# design.net
KiCad netlist of a schematic drawn in Altium Designer
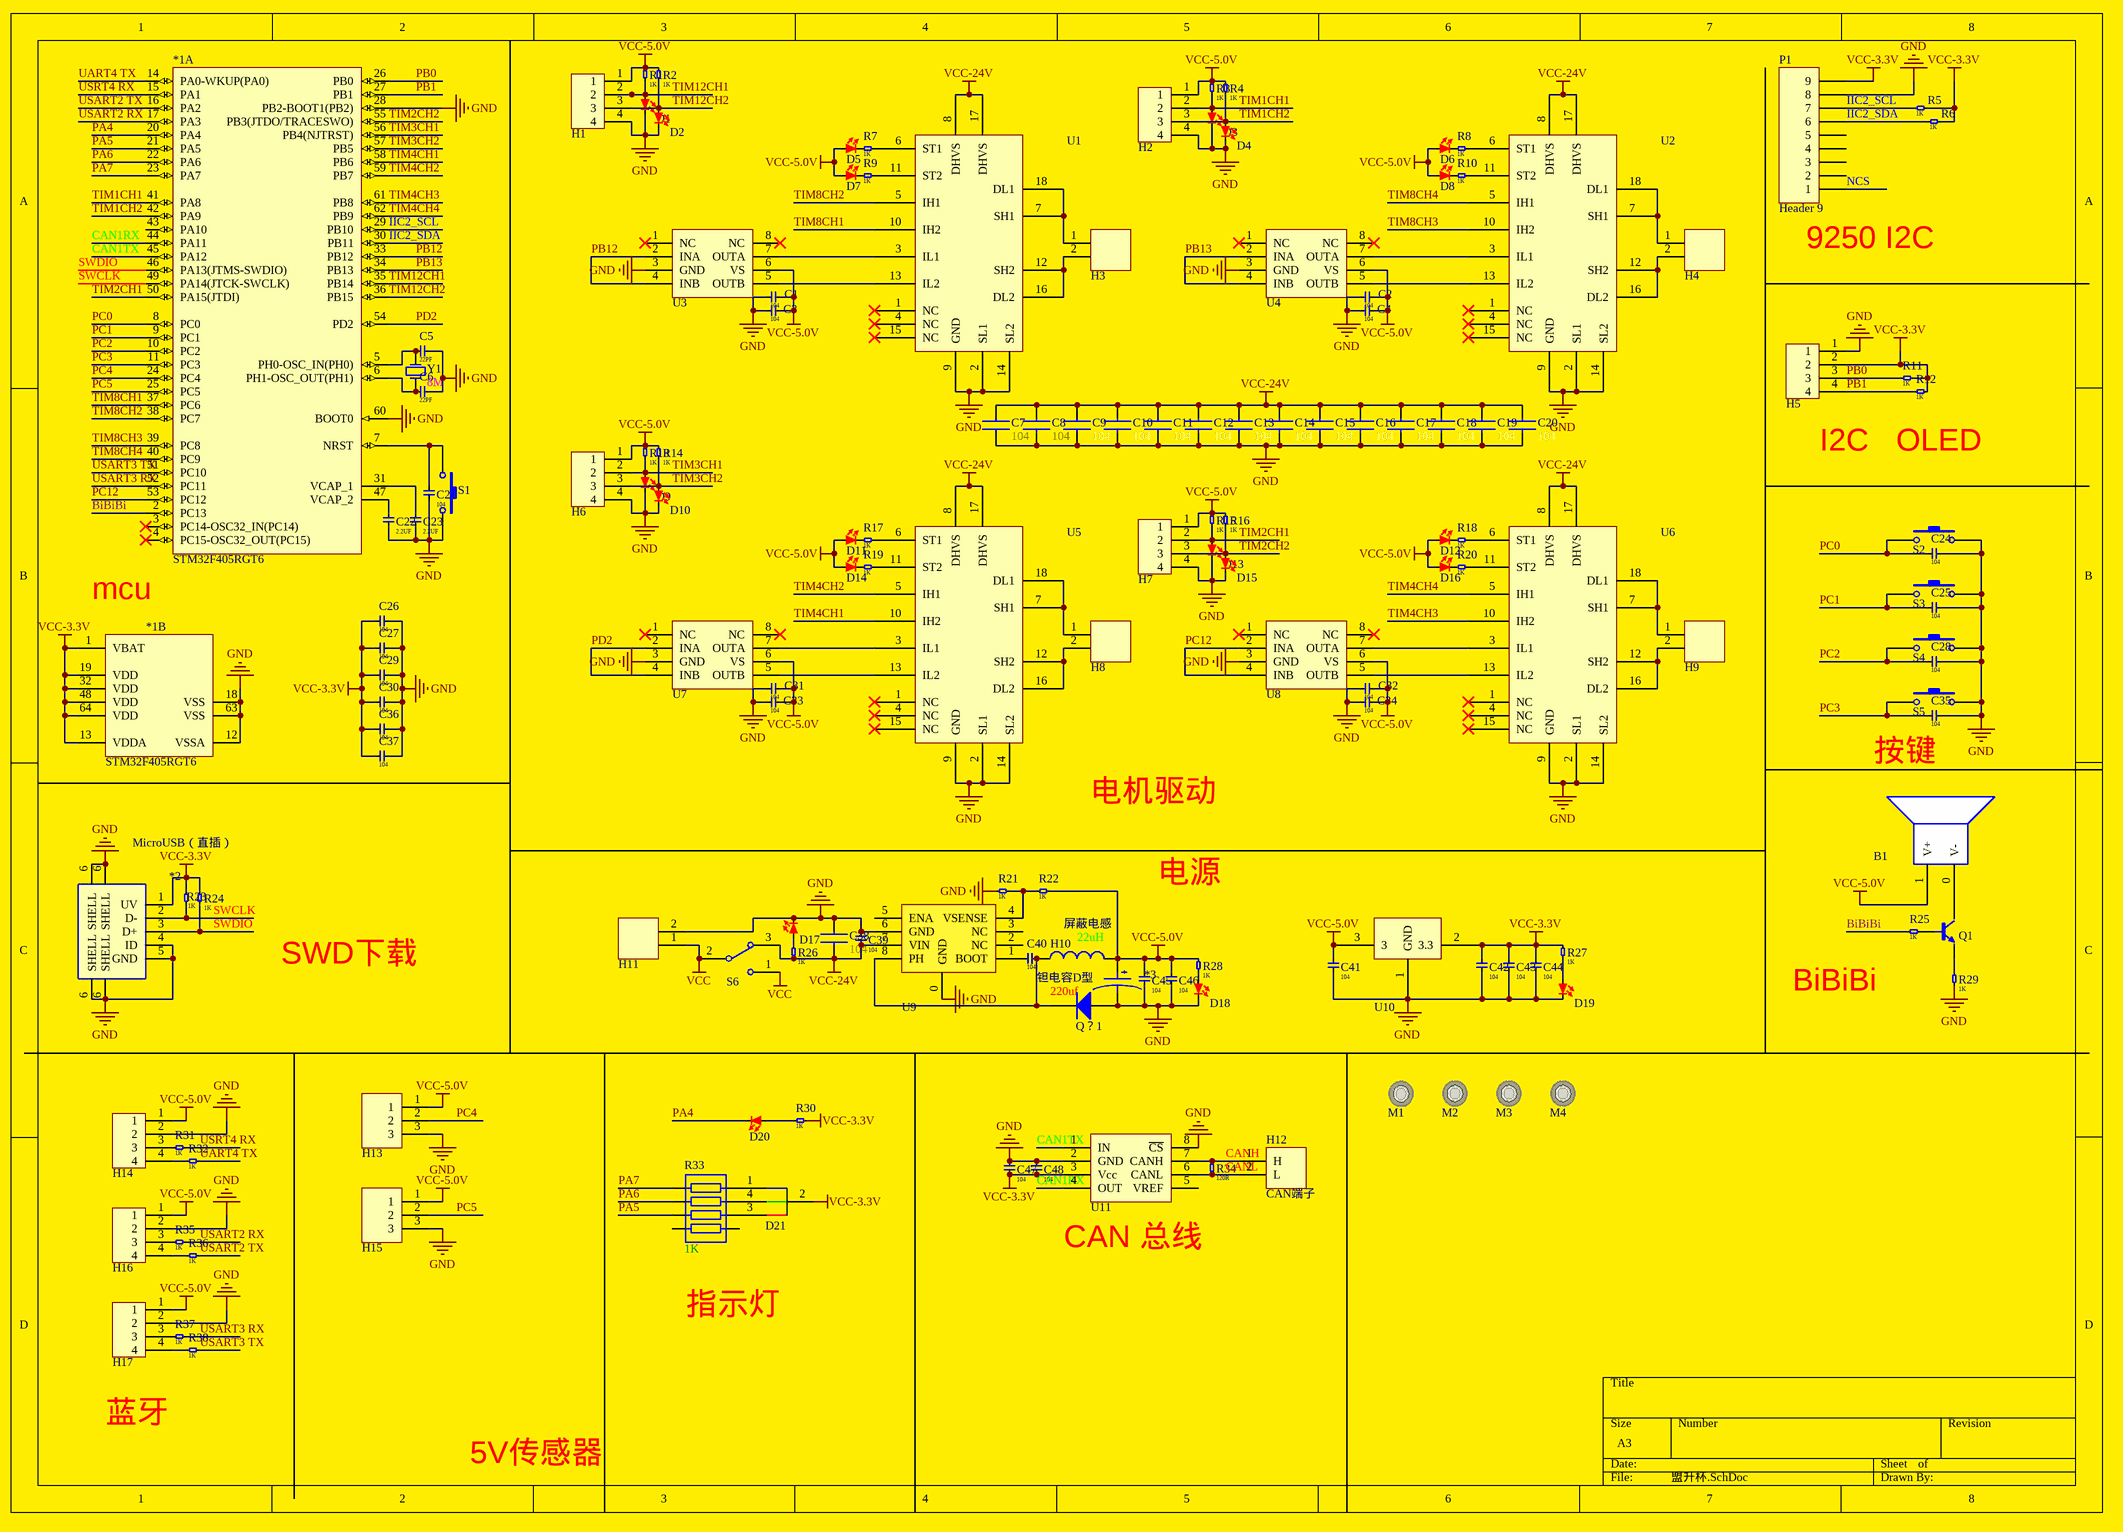
[diagram p0: 盟升杯.SchDoc]

(export (version "E")
  (design (tool "Eeschema 10.0.6"))
  (components
    (comp (ref "*1")
      (value "STM32F405RGT6")
      (footprint "LQFP_64P")
      (libsource (lib "固执啊啊啊啊啊（方林的封装库）7.24") (part "STM32F405RGT6"))
    )
    (comp (ref "*2")
      (value "MicroUSB（直插）")
      (footprint "MicroUSB（直插）")
      (libsource (lib "固执啊啊啊啊啊（方林的封装库）7.24") (part "MicroUSB（直插）"))
    )
    (comp (ref "*3")
      (value "钽电容D型")
      (footprint "钽电容D型")
      (fields (field (name "ALTIUM_UNNAMED_1") "220uf"))
      (libsource (lib "固执啊啊啊啊啊（方林的封装库）7.24") (part "钽电容D型"))
    )
    (comp (ref "B1")
      (value "KLJ-9032")
      (footprint "KLJ-9032")
      (description "贴片蜂鸣器")
      (libsource (lib "固执啊啊啊啊啊（方林的封装库）7.24") (part "KLJ-9032"))
    )
    (comp (ref "C1")
      (value "CAP0603")
      (footprint "CAP0603")
      (fields (field (name "ALTIUM_UNNAMED_1") "104"))
      (libsource (lib "固执啊啊啊啊啊（方林的封装库）7.24") (part "CAP0603"))
    )
    (comp (ref "C2")
      (value "CAP0603")
      (footprint "CAP0603")
      (fields (field (name "ALTIUM_UNNAMED_1") "104"))
      (libsource (lib "固执啊啊啊啊啊（方林的封装库）7.24") (part "CAP0603"))
    )
    (comp (ref "C3")
      (value "CAP0603")
      (footprint "CAP0603")
      (fields (field (name "ALTIUM_UNNAMED_1") "104"))
      (libsource (lib "固执啊啊啊啊啊（方林的封装库）7.24") (part "CAP0603"))
    )
    (comp (ref "C4")
      (value "CAP0603")
      (footprint "CAP0603")
      (fields (field (name "ALTIUM_UNNAMED_1") "104"))
      (libsource (lib "固执啊啊啊啊啊（方林的封装库）7.24") (part "CAP0603"))
    )
    (comp (ref "C5")
      (value "CAP0603")
      (footprint "CAP0603")
      (fields (field (name "ALTIUM_UNNAMED_1") "22PF"))
      (libsource (lib "固执啊啊啊啊啊（方林的封装库）7.24") (part "CAP0603"))
    )
    (comp (ref "C6")
      (value "CAP0603")
      (footprint "CAP0603")
      (fields (field (name "ALTIUM_UNNAMED_1") "22PF"))
      (libsource (lib "固执啊啊啊啊啊（方林的封装库）7.24") (part "CAP0603"))
    )
    (comp (ref "C7")
      (value "CAP1812")
      (footprint "CAP1812")
      (fields (field (name "ALTIUM_UNNAMED_1") "104"))
      (libsource (lib "固执啊啊啊啊啊（方林的封装库）7.24") (part "CAP1812"))
    )
    (comp (ref "C8")
      (value "CAP1812")
      (footprint "CAP1812")
      (fields (field (name "ALTIUM_UNNAMED_1") "104"))
      (libsource (lib "固执啊啊啊啊啊（方林的封装库）7.24") (part "CAP1812"))
    )
    (comp (ref "C9")
      (value "CAP1210")
      (footprint "CAP1210")
      (fields (field (name "ALTIUM_UNNAMED_1") "104"))
      (libsource (lib "固执啊啊啊啊啊（方林的封装库）7.24") (part "CAP1210"))
    )
    (comp (ref "C10")
      (value "CAP1210")
      (footprint "CAP1210")
      (fields (field (name "ALTIUM_UNNAMED_1") "104"))
      (libsource (lib "固执啊啊啊啊啊（方林的封装库）7.24") (part "CAP1210"))
    )
    (comp (ref "C11")
      (value "CAP1210")
      (footprint "CAP1210")
      (fields (field (name "ALTIUM_UNNAMED_1") "104"))
      (libsource (lib "固执啊啊啊啊啊（方林的封装库）7.24") (part "CAP1210"))
    )
    (comp (ref "C12")
      (value "CAP1210")
      (footprint "CAP1210")
      (fields (field (name "ALTIUM_UNNAMED_1") "104"))
      (libsource (lib "固执啊啊啊啊啊（方林的封装库）7.24") (part "CAP1210"))
    )
    (comp (ref "C13")
      (value "CAP1210")
      (footprint "CAP1210")
      (fields (field (name "ALTIUM_UNNAMED_1") "104"))
      (libsource (lib "固执啊啊啊啊啊（方林的封装库）7.24") (part "CAP1210"))
    )
    (comp (ref "C14")
      (value "CAP1210")
      (footprint "CAP1210")
      (fields (field (name "ALTIUM_UNNAMED_1") "104"))
      (libsource (lib "固执啊啊啊啊啊（方林的封装库）7.24") (part "CAP1210"))
    )
    (comp (ref "C15")
      (value "CAP1210")
      (footprint "CAP1210")
      (fields (field (name "ALTIUM_UNNAMED_1") "104"))
      (libsource (lib "固执啊啊啊啊啊（方林的封装库）7.24") (part "CAP1210"))
    )
    (comp (ref "C16")
      (value "CAP1210")
      (footprint "CAP1210")
      (fields (field (name "ALTIUM_UNNAMED_1") "104"))
      (libsource (lib "固执啊啊啊啊啊（方林的封装库）7.24") (part "CAP1210"))
    )
    (comp (ref "C17")
      (value "CAP1210")
      (footprint "CAP1210")
      (fields (field (name "ALTIUM_UNNAMED_1") "104"))
      (libsource (lib "固执啊啊啊啊啊（方林的封装库）7.24") (part "CAP1210"))
    )
    (comp (ref "C18")
      (value "CAP1210")
      (footprint "CAP1210")
      (fields (field (name "ALTIUM_UNNAMED_1") "104"))
      (libsource (lib "固执啊啊啊啊啊（方林的封装库）7.24") (part "CAP1210"))
    )
    (comp (ref "C19")
      (value "CAP1210")
      (footprint "CAP1210")
      (fields (field (name "ALTIUM_UNNAMED_1") "104"))
      (libsource (lib "固执啊啊啊啊啊（方林的封装库）7.24") (part "CAP1210"))
    )
    (comp (ref "C20")
      (value "CAP1210")
      (footprint "CAP1210")
      (fields (field (name "ALTIUM_UNNAMED_1") "104"))
      (libsource (lib "固执啊啊啊啊啊（方林的封装库）7.24") (part "CAP1210"))
    )
    (comp (ref "C21")
      (value "CAP0603")
      (footprint "CAP0603")
      (fields (field (name "ALTIUM_UNNAMED_1") "104"))
      (libsource (lib "固执啊啊啊啊啊（方林的封装库）7.24") (part "CAP0603"))
    )
    (comp (ref "C22")
      (value "CAP0603")
      (footprint "CAP0603")
      (fields (field (name "ALTIUM_UNNAMED_1") "2.2UF"))
      (libsource (lib "固执啊啊啊啊啊（方林的封装库）7.24") (part "CAP0603"))
    )
    (comp (ref "C23")
      (value "CAP0603")
      (footprint "CAP0603")
      (fields (field (name "ALTIUM_UNNAMED_1") "2.2UF"))
      (libsource (lib "固执啊啊啊啊啊（方林的封装库）7.24") (part "CAP0603"))
    )
    (comp (ref "C24")
      (value "CAP0603")
      (footprint "CAP0603")
      (fields (field (name "ALTIUM_UNNAMED_1") "104"))
      (libsource (lib "固执啊啊啊啊啊（方林的封装库）7.24") (part "CAP0603"))
    )
    (comp (ref "C25")
      (value "CAP0603")
      (footprint "CAP0603")
      (fields (field (name "ALTIUM_UNNAMED_1") "104"))
      (libsource (lib "固执啊啊啊啊啊（方林的封装库）7.24") (part "CAP0603"))
    )
    (comp (ref "C26")
      (value "CAP0603")
      (footprint "CAP0603")
      (fields (field (name "ALTIUM_UNNAMED_1") "104"))
      (libsource (lib "固执啊啊啊啊啊（方林的封装库）7.24") (part "CAP0603"))
    )
    (comp (ref "C27")
      (value "CAP0603")
      (footprint "CAP0603")
      (fields (field (name "ALTIUM_UNNAMED_1") "104"))
      (libsource (lib "固执啊啊啊啊啊（方林的封装库）7.24") (part "CAP0603"))
    )
    (comp (ref "C28")
      (value "CAP0603")
      (footprint "CAP0603")
      (fields (field (name "ALTIUM_UNNAMED_1") "104"))
      (libsource (lib "固执啊啊啊啊啊（方林的封装库）7.24") (part "CAP0603"))
    )
    (comp (ref "C29")
      (value "CAP0603")
      (footprint "CAP0603")
      (fields (field (name "ALTIUM_UNNAMED_1") "104"))
      (libsource (lib "固执啊啊啊啊啊（方林的封装库）7.24") (part "CAP0603"))
    )
    (comp (ref "C30")
      (value "CAP0603")
      (footprint "CAP0603")
      (fields (field (name "ALTIUM_UNNAMED_1") "104"))
      (libsource (lib "固执啊啊啊啊啊（方林的封装库）7.24") (part "CAP0603"))
    )
    (comp (ref "C31")
      (value "CAP0603")
      (footprint "CAP0603")
      (fields (field (name "ALTIUM_UNNAMED_1") "104"))
      (libsource (lib "固执啊啊啊啊啊（方林的封装库）7.24") (part "CAP0603"))
    )
    (comp (ref "C32")
      (value "CAP0603")
      (footprint "CAP0603")
      (fields (field (name "ALTIUM_UNNAMED_1") "104"))
      (libsource (lib "固执啊啊啊啊啊（方林的封装库）7.24") (part "CAP0603"))
    )
    (comp (ref "C33")
      (value "CAP0603")
      (footprint "CAP0603")
      (fields (field (name "ALTIUM_UNNAMED_1") "104"))
      (libsource (lib "固执啊啊啊啊啊（方林的封装库）7.24") (part "CAP0603"))
    )
    (comp (ref "C34")
      (value "CAP0603")
      (footprint "CAP0603")
      (fields (field (name "ALTIUM_UNNAMED_1") "104"))
      (libsource (lib "固执啊啊啊啊啊（方林的封装库）7.24") (part "CAP0603"))
    )
    (comp (ref "C35")
      (value "CAP0603")
      (footprint "CAP0603")
      (fields (field (name "ALTIUM_UNNAMED_1") "104"))
      (libsource (lib "固执啊啊啊啊啊（方林的封装库）7.24") (part "CAP0603"))
    )
    (comp (ref "C36")
      (value "CAP0603")
      (footprint "CAP0603")
      (fields (field (name "ALTIUM_UNNAMED_1") "104"))
      (libsource (lib "固执啊啊啊啊啊（方林的封装库）7.24") (part "CAP0603"))
    )
    (comp (ref "C37")
      (value "CAP0603")
      (footprint "CAP0603")
      (fields (field (name "ALTIUM_UNNAMED_1") "104"))
      (libsource (lib "固执啊啊啊啊啊（方林的封装库）7.24") (part "CAP0603"))
    )
    (comp (ref "C38")
      (value "CAP1812")
      (footprint "CAP1812")
      (fields (field (name "ALTIUM_UNNAMED_1") "104"))
      (libsource (lib "固执啊啊啊啊啊（方林的封装库）7.24") (part "CAP1812"))
    )
    (comp (ref "C39")
      (value "CAP0603")
      (footprint "CAP0603")
      (fields (field (name "ALTIUM_UNNAMED_1") "104"))
      (libsource (lib "固执啊啊啊啊啊（方林的封装库）7.24") (part "CAP0603"))
    )
    (comp (ref "C40")
      (value "CAP0603")
      (footprint "CAP0603")
      (fields (field (name "ALTIUM_UNNAMED_1") "104"))
      (libsource (lib "固执啊啊啊啊啊（方林的封装库）7.24") (part "CAP0603"))
    )
    (comp (ref "C41")
      (value "CAP0603")
      (footprint "CAP0603")
      (fields (field (name "ALTIUM_UNNAMED_1") "104"))
      (libsource (lib "固执啊啊啊啊啊（方林的封装库）7.24") (part "CAP0603"))
    )
    (comp (ref "C42")
      (value "CAP0603")
      (footprint "CAP0603")
      (fields (field (name "ALTIUM_UNNAMED_1") "104"))
      (libsource (lib "固执啊啊啊啊啊（方林的封装库）7.24") (part "CAP0603"))
    )
    (comp (ref "C43")
      (value "CAP0603")
      (footprint "CAP0603")
      (fields (field (name "ALTIUM_UNNAMED_1") "104"))
      (libsource (lib "固执啊啊啊啊啊（方林的封装库）7.24") (part "CAP0603"))
    )
    (comp (ref "C44")
      (value "CAP0603")
      (footprint "CAP0603")
      (fields (field (name "ALTIUM_UNNAMED_1") "104"))
      (libsource (lib "固执啊啊啊啊啊（方林的封装库）7.24") (part "CAP0603"))
    )
    (comp (ref "C45")
      (value "CAP0603")
      (footprint "CAP0603")
      (fields (field (name "ALTIUM_UNNAMED_1") "104"))
      (libsource (lib "固执啊啊啊啊啊（方林的封装库）7.24") (part "CAP0603"))
    )
    (comp (ref "C46")
      (value "CAP0603")
      (footprint "CAP0603")
      (fields (field (name "ALTIUM_UNNAMED_1") "104"))
      (libsource (lib "固执啊啊啊啊啊（方林的封装库）7.24") (part "CAP0603"))
    )
    (comp (ref "C47")
      (value "CAP0603")
      (footprint "CAP0603")
      (fields (field (name "ALTIUM_UNNAMED_1") "104"))
      (libsource (lib "固执啊啊啊啊啊（方林的封装库）7.24") (part "CAP0603"))
    )
    (comp (ref "C48")
      (value "104")
      (footprint "CAP")
      (fields (field (name "ALTIUM_UNNAMED_1") "104"))
      (libsource (lib "固执啊啊啊啊啊（方林的封装库）7.24") (part "CAP0805"))
    )
    (comp (ref "D1")
      (value "LED")
      (footprint "LED_0603_B")
      (libsource (lib "固执啊啊啊啊啊（方林的封装库）7.24") (part "LED"))
    )
    (comp (ref "D2")
      (value "LED")
      (footprint "LED_0603_B")
      (libsource (lib "固执啊啊啊啊啊（方林的封装库）7.24") (part "LED"))
    )
    (comp (ref "D3")
      (value "LED")
      (footprint "LED_0603_B")
      (libsource (lib "固执啊啊啊啊啊（方林的封装库）7.24") (part "LED"))
    )
    (comp (ref "D4")
      (value "LED")
      (footprint "LED_0603_B")
      (libsource (lib "固执啊啊啊啊啊（方林的封装库）7.24") (part "LED"))
    )
    (comp (ref "D5")
      (value "LED")
      (footprint "LED_0603_B")
      (libsource (lib "固执啊啊啊啊啊（方林的封装库）7.24") (part "LED"))
    )
    (comp (ref "D6")
      (value "LED")
      (footprint "LED_0603_B")
      (libsource (lib "固执啊啊啊啊啊（方林的封装库）7.24") (part "LED"))
    )
    (comp (ref "D7")
      (value "LED")
      (footprint "LED_0603_G")
      (libsource (lib "固执啊啊啊啊啊（方林的封装库）7.24") (part "LED"))
    )
    (comp (ref "D8")
      (value "LED")
      (footprint "LED_0603_G")
      (libsource (lib "固执啊啊啊啊啊（方林的封装库）7.24") (part "LED"))
    )
    (comp (ref "D9")
      (value "LED")
      (footprint "LED_0603_B")
      (libsource (lib "固执啊啊啊啊啊（方林的封装库）7.24") (part "LED"))
    )
    (comp (ref "D10")
      (value "LED")
      (footprint "LED_0603_B")
      (libsource (lib "固执啊啊啊啊啊（方林的封装库）7.24") (part "LED"))
    )
    (comp (ref "D11")
      (value "LED")
      (footprint "LED_0603_B")
      (libsource (lib "固执啊啊啊啊啊（方林的封装库）7.24") (part "LED"))
    )
    (comp (ref "D12")
      (value "LED")
      (footprint "LED_0603_B")
      (libsource (lib "固执啊啊啊啊啊（方林的封装库）7.24") (part "LED"))
    )
    (comp (ref "D13")
      (value "LED")
      (footprint "LED_0603_B")
      (libsource (lib "固执啊啊啊啊啊（方林的封装库）7.24") (part "LED"))
    )
    (comp (ref "D14")
      (value "LED")
      (footprint "LED_0603_G")
      (libsource (lib "固执啊啊啊啊啊（方林的封装库）7.24") (part "LED"))
    )
    (comp (ref "D15")
      (value "LED")
      (footprint "LED_0603_B")
      (libsource (lib "固执啊啊啊啊啊（方林的封装库）7.24") (part "LED"))
    )
    (comp (ref "D16")
      (value "LED")
      (footprint "LED_0603_G")
      (libsource (lib "固执啊啊啊啊啊（方林的封装库）7.24") (part "LED"))
    )
    (comp (ref "D17")
      (value "LED")
      (footprint "LED_0603_R")
      (libsource (lib "固执啊啊啊啊啊（方林的封装库）7.24") (part "LED"))
    )
    (comp (ref "D18")
      (value "LED")
      (footprint "LED_0603_R")
      (libsource (lib "固执啊啊啊啊啊（方林的封装库）7.24") (part "LED"))
    )
    (comp (ref "D19")
      (value "LED")
      (footprint "LED_0603_R")
      (libsource (lib "固执啊啊啊啊啊（方林的封装库）7.24") (part "LED"))
    )
    (comp (ref "D20")
      (value "LED")
      (footprint "LED_0603_R")
      (libsource (lib "固执啊啊啊啊啊（方林的封装库）7.24") (part "LED"))
    )
    (comp (ref "D21")
      (value "RGB")
      (footprint "RGB")
      (description "三色LED")
      (libsource (lib "固执啊啊啊啊啊（方林的封装库）7.24") (part "RGB"))
    )
    (comp (ref "H1")
      (value "H4")
      (footprint "H4_WHITE")
      (description "排针")
      (libsource (lib "固执啊啊啊啊啊（方林的封装库）7.24") (part "H4"))
    )
    (comp (ref "H2")
      (value "H4")
      (footprint "H4_WHITE")
      (description "排针")
      (libsource (lib "固执啊啊啊啊啊（方林的封装库）7.24") (part "H4"))
    )
    (comp (ref "H3")
      (value "H2 POWER")
      (footprint "H2 POWER")
      (libsource (lib "固执啊啊啊啊啊（方林的封装库）7.24") (part "H2 POWER"))
    )
    (comp (ref "H4")
      (value "H2 POWER")
      (footprint "H2 POWER")
      (libsource (lib "固执啊啊啊啊啊（方林的封装库）7.24") (part "H2 POWER"))
    )
    (comp (ref "H5")
      (value "H4")
      (footprint "H4")
      (description "排针")
      (libsource (lib "固执啊啊啊啊啊（方林的封装库）7.24") (part "H4"))
    )
    (comp (ref "H6")
      (value "H4")
      (footprint "H4_WHITE")
      (description "排针")
      (libsource (lib "固执啊啊啊啊啊（方林的封装库）7.24") (part "H4"))
    )
    (comp (ref "H7")
      (value "H4")
      (footprint "H4_WHITE")
      (description "排针")
      (libsource (lib "固执啊啊啊啊啊（方林的封装库）7.24") (part "H4"))
    )
    (comp (ref "H8")
      (value "H2 POWER")
      (footprint "H2 POWER")
      (libsource (lib "固执啊啊啊啊啊（方林的封装库）7.24") (part "H2 POWER"))
    )
    (comp (ref "H9")
      (value "H2 POWER")
      (footprint "H2 POWER")
      (libsource (lib "固执啊啊啊啊啊（方林的封装库）7.24") (part "H2 POWER"))
    )
    (comp (ref "H10")
      (value "屏蔽电感")
      (footprint "屏蔽7.2*7.2")
      (fields (field (name "ALTIUM_UNNAMED_1") "22uH"))
      (libsource (lib "固执啊啊啊啊啊（方林的封装库）7.24") (part "屏蔽电感"))
    )
    (comp (ref "H11") (value "H2 POWER") (footprint "H2 POWER") (libsource (lib "") (part "H2 POWER_1")))
    (comp (ref "H12")
      (value "CAN端子")
      (footprint "CAN端子")
      (libsource (lib "固执啊啊啊啊啊（方林的封装库）7.24") (part "CAN端子"))
    )
    (comp (ref "H13")
      (value "H3")
      (footprint "H3_WHITE")
      (description "排针")
      (libsource (lib "固执啊啊啊啊啊（方林的封装库）7.24") (part "H3"))
    )
    (comp (ref "H14")
      (value "H4")
      (footprint "H4")
      (description "排针")
      (libsource (lib "固执啊啊啊啊啊（方林的封装库）7.24") (part "H4"))
    )
    (comp (ref "H15")
      (value "H3")
      (footprint "H3_WHITE")
      (description "排针")
      (libsource (lib "固执啊啊啊啊啊（方林的封装库）7.24") (part "H3"))
    )
    (comp (ref "H16")
      (value "H4")
      (footprint "H4")
      (description "排针")
      (libsource (lib "固执啊啊啊啊啊（方林的封装库）7.24") (part "H4"))
    )
    (comp (ref "H17")
      (value "H4")
      (footprint "H4")
      (description "排针")
      (libsource (lib "固执啊啊啊啊啊（方林的封装库）7.24") (part "H4"))
    )
    (comp (ref "M1") (value "M3过孔") (footprint "M3过孔") (libsource (lib "固执啊啊啊啊啊（方林的封装库）7.24") (part "M3过孔")))
    (comp (ref "M2") (value "M3过孔") (footprint "M3过孔") (libsource (lib "固执啊啊啊啊啊（方林的封装库）7.24") (part "M3过孔")))
    (comp (ref "M3") (value "M3过孔") (footprint "M3过孔") (libsource (lib "固执啊啊啊啊啊（方林的封装库）7.24") (part "M3过孔")))
    (comp (ref "M4") (value "M3过孔") (footprint "M3过孔") (libsource (lib "固执啊啊啊啊啊（方林的封装库）7.24") (part "M3过孔")))
    (comp (ref "P1")
      (value "Header 9")
      (footprint "HDR1X9")
      (description "Header, 9-Pin")
      (fields (field (name "PUBLISHER") "Altium Limited"))
      (libsource (lib "Miscellaneous Connectors") (part "Header 9"))
    )
    (comp (ref "Q1")
      (value "2N5551")
      (footprint "2N5551")
      (description "NPN三极管")
      (libsource (lib "固执啊啊啊啊啊（方林的封装库）7.24") (part "2N5551"))
    )
    (comp (ref "Q？1")
      (value "SS34")
      (footprint "SS34")
      (description "肖特基二极管")
      (libsource (lib "固执啊啊啊啊啊（方林的封装库）7.24") (part "SS34"))
    )
    (comp (ref "R1")
      (value "电阻R")
      (footprint "R0603")
      (fields (field (name "ALTIUM_UNNAMED_1") "1K"))
      (libsource (lib "") (part "电阻R_1"))
    )
    (comp (ref "R2")
      (value "电阻R")
      (footprint "R0603")
      (fields (field (name "ALTIUM_UNNAMED_1") "1K"))
      (libsource (lib "") (part "电阻R_1"))
    )
    (comp (ref "R3")
      (value "电阻R")
      (footprint "R0603")
      (fields (field (name "ALTIUM_UNNAMED_1") "1K"))
      (libsource (lib "") (part "电阻R_1"))
    )
    (comp (ref "R4")
      (value "电阻R")
      (footprint "R0603")
      (fields (field (name "ALTIUM_UNNAMED_1") "1K"))
      (libsource (lib "") (part "电阻R_1"))
    )
    (comp (ref "R5")
      (value "电阻R")
      (footprint "R0603")
      (fields (field (name "ALTIUM_UNNAMED_1") "1K"))
      (libsource (lib "固执啊啊啊啊啊（方林的封装库）7.24") (part "电阻R"))
    )
    (comp (ref "R6")
      (value "电阻R")
      (footprint "R0603")
      (fields (field (name "ALTIUM_UNNAMED_1") "1K"))
      (libsource (lib "固执啊啊啊啊啊（方林的封装库）7.24") (part "电阻R"))
    )
    (comp (ref "R7")
      (value "电阻R")
      (footprint "R0603")
      (fields (field (name "ALTIUM_UNNAMED_1") "1K"))
      (libsource (lib "固执啊啊啊啊啊（方林的封装库）7.24") (part "电阻R"))
    )
    (comp (ref "R8")
      (value "电阻R")
      (footprint "R0603")
      (fields (field (name "ALTIUM_UNNAMED_1") "1K"))
      (libsource (lib "固执啊啊啊啊啊（方林的封装库）7.24") (part "电阻R"))
    )
    (comp (ref "R9")
      (value "电阻R")
      (footprint "R0603")
      (fields (field (name "ALTIUM_UNNAMED_1") "1K"))
      (libsource (lib "固执啊啊啊啊啊（方林的封装库）7.24") (part "电阻R"))
    )
    (comp (ref "R10")
      (value "电阻R")
      (footprint "R0603")
      (fields (field (name "ALTIUM_UNNAMED_1") "1K"))
      (libsource (lib "固执啊啊啊啊啊（方林的封装库）7.24") (part "电阻R"))
    )
    (comp (ref "R11")
      (value "电阻R")
      (footprint "R0603")
      (fields (field (name "ALTIUM_UNNAMED_1") "1K"))
      (libsource (lib "固执啊啊啊啊啊（方林的封装库）7.24") (part "电阻R"))
    )
    (comp (ref "R12")
      (value "电阻R")
      (footprint "R0805")
      (fields (field (name "ALTIUM_UNNAMED_1") "1K"))
      (libsource (lib "固执啊啊啊啊啊（方林的封装库）7.24") (part "电阻R"))
    )
    (comp (ref "R13")
      (value "电阻R")
      (footprint "R0603")
      (fields (field (name "ALTIUM_UNNAMED_1") "1K"))
      (libsource (lib "") (part "电阻R_1"))
    )
    (comp (ref "R14")
      (value "电阻R")
      (footprint "R0603")
      (fields (field (name "ALTIUM_UNNAMED_1") "1K"))
      (libsource (lib "") (part "电阻R_1"))
    )
    (comp (ref "R15")
      (value "电阻R")
      (footprint "R0603")
      (fields (field (name "ALTIUM_UNNAMED_1") "1K"))
      (libsource (lib "") (part "电阻R_1"))
    )
    (comp (ref "R16")
      (value "电阻R")
      (footprint "R0603")
      (fields (field (name "ALTIUM_UNNAMED_1") "1K"))
      (libsource (lib "") (part "电阻R_1"))
    )
    (comp (ref "R17")
      (value "电阻R")
      (footprint "R0603")
      (fields (field (name "ALTIUM_UNNAMED_1") "1K"))
      (libsource (lib "固执啊啊啊啊啊（方林的封装库）7.24") (part "电阻R"))
    )
    (comp (ref "R18")
      (value "电阻R")
      (footprint "R0603")
      (fields (field (name "ALTIUM_UNNAMED_1") "1K"))
      (libsource (lib "固执啊啊啊啊啊（方林的封装库）7.24") (part "电阻R"))
    )
    (comp (ref "R19")
      (value "电阻R")
      (footprint "R0603")
      (fields (field (name "ALTIUM_UNNAMED_1") "1K"))
      (libsource (lib "固执啊啊啊啊啊（方林的封装库）7.24") (part "电阻R"))
    )
    (comp (ref "R20")
      (value "电阻R")
      (footprint "R0603")
      (fields (field (name "ALTIUM_UNNAMED_1") "1K"))
      (libsource (lib "固执啊啊啊啊啊（方林的封装库）7.24") (part "电阻R"))
    )
    (comp (ref "R21")
      (value "电阻R")
      (footprint "R0603")
      (fields (field (name "ALTIUM_UNNAMED_1") "1K"))
      (libsource (lib "固执啊啊啊啊啊（方林的封装库）7.24") (part "电阻R"))
    )
    (comp (ref "R22")
      (value "电阻R")
      (footprint "R0603")
      (fields (field (name "ALTIUM_UNNAMED_1") "1K"))
      (libsource (lib "固执啊啊啊啊啊（方林的封装库）7.24") (part "电阻R"))
    )
    (comp (ref "R23")
      (value "电阻R")
      (footprint "R0603")
      (fields (field (name "ALTIUM_UNNAMED_1") "1K"))
      (libsource (lib "") (part "电阻R_1"))
    )
    (comp (ref "R24")
      (value "电阻R")
      (footprint "R0603")
      (fields (field (name "ALTIUM_UNNAMED_1") "1K"))
      (libsource (lib "") (part "电阻R_1"))
    )
    (comp (ref "R25")
      (value "电阻R")
      (footprint "R0603")
      (fields (field (name "ALTIUM_UNNAMED_1") "1K"))
      (libsource (lib "固执啊啊啊啊啊（方林的封装库）7.24") (part "电阻R"))
    )
    (comp (ref "R26")
      (value "电阻R")
      (footprint "R0603")
      (fields (field (name "ALTIUM_UNNAMED_1") "1K"))
      (libsource (lib "") (part "电阻R_1"))
    )
    (comp (ref "R27")
      (value "电阻R")
      (footprint "R0603")
      (fields (field (name "ALTIUM_UNNAMED_1") "1K"))
      (libsource (lib "固执啊啊啊啊啊（方林的封装库）7.24") (part "电阻R"))
    )
    (comp (ref "R28")
      (value "电阻R")
      (footprint "R0603")
      (fields (field (name "ALTIUM_UNNAMED_1") "1K"))
      (libsource (lib "固执啊啊啊啊啊（方林的封装库）7.24") (part "电阻R"))
    )
    (comp (ref "R29")
      (value "电阻R")
      (footprint "R0603")
      (fields (field (name "ALTIUM_UNNAMED_1") "1K"))
      (libsource (lib "") (part "电阻R_1"))
    )
    (comp (ref "R30")
      (value "电阻R")
      (footprint "R0603")
      (fields (field (name "ALTIUM_UNNAMED_1") "1K"))
      (libsource (lib "") (part "电阻R_1"))
    )
    (comp (ref "R31")
      (value "电阻R")
      (footprint "R0603")
      (fields (field (name "ALTIUM_UNNAMED_1") "1K"))
      (libsource (lib "固执啊啊啊啊啊（方林的封装库）7.24") (part "电阻R"))
    )
    (comp (ref "R32")
      (value "电阻R")
      (footprint "R0603")
      (fields (field (name "ALTIUM_UNNAMED_1") "1K"))
      (libsource (lib "固执啊啊啊啊啊（方林的封装库）7.24") (part "电阻R"))
    )
    (comp (ref "R33")
      (value "1K*4排阻")
      (footprint "1K*4排阻")
      (fields (field (name "ALTIUM_UNNAMED_1") "1K"))
      (libsource (lib "固执啊啊啊啊啊（方林的封装库）7.24") (part "1K*4排阻"))
    )
    (comp (ref "R34")
      (value "电阻R")
      (footprint "R0603")
      (fields (field (name "ALTIUM_UNNAMED_1") "120R"))
      (libsource (lib "") (part "电阻R_1"))
    )
    (comp (ref "R35")
      (value "电阻R")
      (footprint "R0603")
      (fields (field (name "ALTIUM_UNNAMED_1") "1K"))
      (libsource (lib "固执啊啊啊啊啊（方林的封装库）7.24") (part "电阻R"))
    )
    (comp (ref "R36")
      (value "电阻R")
      (footprint "R0603")
      (fields (field (name "ALTIUM_UNNAMED_1") "1K"))
      (libsource (lib "固执啊啊啊啊啊（方林的封装库）7.24") (part "电阻R"))
    )
    (comp (ref "R37")
      (value "电阻R")
      (footprint "R0603")
      (fields (field (name "ALTIUM_UNNAMED_1") "1K"))
      (libsource (lib "固执啊啊啊啊啊（方林的封装库）7.24") (part "电阻R"))
    )
    (comp (ref "R38")
      (value "电阻R")
      (footprint "R0603")
      (fields (field (name "ALTIUM_UNNAMED_1") "1K"))
      (libsource (lib "固执啊啊啊啊啊（方林的封装库）7.24") (part "电阻R"))
    )
    (comp (ref "S1")
      (value "SWITCH")
      (footprint "SWITCH")
      (description "按键")
      (libsource (lib "固执啊啊啊啊啊（方林的封装库）7.24") (part "SWITCH"))
    )
    (comp (ref "S2")
      (value "SWITCH")
      (footprint "SWITCH")
      (description "按键")
      (libsource (lib "固执啊啊啊啊啊（方林的封装库）7.24") (part "SWITCH"))
    )
    (comp (ref "S3")
      (value "SWITCH")
      (footprint "SWITCH")
      (description "按键")
      (libsource (lib "固执啊啊啊啊啊（方林的封装库）7.24") (part "SWITCH"))
    )
    (comp (ref "S4")
      (value "SWITCH")
      (footprint "SWITCH")
      (description "按键")
      (libsource (lib "固执啊啊啊啊啊（方林的封装库）7.24") (part "SWITCH"))
    )
    (comp (ref "S5")
      (value "SWITCH")
      (footprint "SWITCH")
      (description "按键")
      (libsource (lib "固执啊啊啊啊啊（方林的封装库）7.24") (part "SWITCH"))
    )
    (comp (ref "S6")
      (value "拨动开关")
      (footprint "拨动开关")
      (description "扭子拨动开关")
      (libsource (lib "固执啊啊啊啊啊（方林的封装库）7.24") (part "拨动开关"))
    )
    (comp (ref "U1")
      (value "BTS7810K")
      (footprint "BTS7810K")
      (description "全桥驱动")
      (libsource (lib "固执啊啊啊啊啊（方林的封装库）7.24") (part "BTS7810K"))
    )
    (comp (ref "U2")
      (value "BTS7810K")
      (footprint "BTS7810K")
      (description "全桥驱动")
      (libsource (lib "固执啊啊啊啊啊（方林的封装库）7.24") (part "BTS7810K"))
    )
    (comp (ref "U3")
      (value "MIC4428")
      (footprint "SOIC-NB-8")
      (description "缓冲器")
      (libsource (lib "固执啊啊啊啊啊（方林的封装库）7.24") (part "MIC4428"))
    )
    (comp (ref "U4")
      (value "MIC4428")
      (footprint "SOIC-NB-8")
      (description "缓冲器")
      (libsource (lib "固执啊啊啊啊啊（方林的封装库）7.24") (part "MIC4428"))
    )
    (comp (ref "U5")
      (value "BTS7810K")
      (footprint "BTS7810K")
      (description "全桥驱动")
      (libsource (lib "固执啊啊啊啊啊（方林的封装库）7.24") (part "BTS7810K"))
    )
    (comp (ref "U6")
      (value "BTS7810K")
      (footprint "BTS7810K")
      (description "全桥驱动")
      (libsource (lib "固执啊啊啊啊啊（方林的封装库）7.24") (part "BTS7810K"))
    )
    (comp (ref "U7")
      (value "MIC4428")
      (footprint "SOIC-NB-8")
      (description "缓冲器")
      (libsource (lib "固执啊啊啊啊啊（方林的封装库）7.24") (part "MIC4428"))
    )
    (comp (ref "U8")
      (value "MIC4428")
      (footprint "SOIC-NB-8")
      (description "缓冲器")
      (libsource (lib "固执啊啊啊啊啊（方林的封装库）7.24") (part "MIC4428"))
    )
    (comp (ref "U9")
      (value "TPS5430")
      (footprint "POWERPARK SOP8")
      (description "开关稳压芯片")
      (libsource (lib "固执啊啊啊啊啊（方林的封装库）7.24") (part "TPS5430"))
    )
    (comp (ref "U10")
      (value "AMS1117")
      (footprint "AMS1117")
      (description "3.3V稳压电源")
      (libsource (lib "固执啊啊啊啊啊（方林的封装库）7.24") (part "AMS1117"))
    )
    (comp (ref "U11")
      (value "VP230")
      (footprint "VP230")
      (description "CAN 芯片")
      (libsource (lib "固执啊啊啊啊啊（方林的封装库）7.24") (part "VP230"))
    )
    (comp (ref "Y1")
      (value "XTAL")
      (footprint "XTAL")
      (description "晶振")
      (fields (field (name "ALTIUM_UNNAMED_1") "8M"))
      (libsource (lib "固执啊啊啊啊啊（方林的封装库）7.24") (part "XTAL"))
    )
  )
  (nets
    (net (code "1") (name "/BiBiBi") (class "Default")
      (node (ref "*1") (pin "2") (pinfunction "PC13_2") (pintype "bidirectional"))
      (node (ref "R25") (pin "1") (pintype "passive"))
    )
    (net (code "2") (name "/CAN1RX") (class "Default")
      (node (ref "*1") (pin "44") (pinfunction "PA11_44") (pintype "bidirectional"))
      (node (ref "U11") (pin "4") (pinfunction "OUT_4") (pintype "passive"))
    )
    (net (code "3") (name "/CAN1TX") (class "Default")
      (node (ref "*1") (pin "45") (pinfunction "PA12_45") (pintype "bidirectional"))
      (node (ref "U11") (pin "1") (pinfunction "IN_1") (pintype "passive"))
    )
    (net (code "4") (name "/CANH") (class "Default")
      (node (ref "H12") (pin "1") (pinfunction "H_1") (pintype "passive"))
      (node (ref "R34") (pin "2") (pintype "passive"))
      (node (ref "U11") (pin "7") (pinfunction "CANH_7") (pintype "passive"))
    )
    (net (code "5") (name "/CANL") (class "Default")
      (node (ref "H12") (pin "2") (pinfunction "L_2") (pintype "passive"))
      (node (ref "R34") (pin "1") (pintype "passive"))
      (node (ref "U11") (pin "6") (pinfunction "CANL_6") (pintype "passive"))
    )
    (net (code "6") (name "/IIC2_SCL") (class "Default")
      (node (ref "*1") (pin "29") (pinfunction "PB10_29") (pintype "bidirectional"))
      (node (ref "P1") (pin "7") (pinfunction "7_7") (pintype "passive"))
      (node (ref "R5") (pin "1") (pintype "passive"))
    )
    (net (code "7") (name "/IIC2_SDA") (class "Default")
      (node (ref "*1") (pin "30") (pinfunction "PB11_30") (pintype "bidirectional"))
      (node (ref "P1") (pin "6") (pinfunction "6_6") (pintype "passive"))
      (node (ref "R6") (pin "1") (pintype "passive"))
    )
    (net (code "8") (name "/NCS") (class "Default")
      (node (ref "P1") (pin "1") (pinfunction "1_1") (pintype "passive"))
    )
    (net (code "9") (name "/PA4") (class "Default")
      (node (ref "*1") (pin "20") (pinfunction "PA4_20") (pintype "bidirectional"))
      (node (ref "D20") (pin "2") (pintype "passive"))
    )
    (net (code "10") (name "/PA5") (class "Default")
      (node (ref "*1") (pin "21") (pinfunction "PA5_21") (pintype "bidirectional"))
      (node (ref "R33") (pin "4") (pintype "passive"))
    )
    (net (code "11") (name "/PA6") (class "Default")
      (node (ref "*1") (pin "22") (pinfunction "PA6_22") (pintype "bidirectional"))
      (node (ref "R33") (pin "6") (pintype "passive"))
    )
    (net (code "12") (name "/PA7") (class "Default")
      (node (ref "*1") (pin "23") (pinfunction "PA7_23") (pintype "bidirectional"))
      (node (ref "R33") (pin "8") (pintype "passive"))
    )
    (net (code "13") (name "/PB0") (class "Default")
      (node (ref "*1") (pin "26") (pinfunction "PB0_26") (pintype "bidirectional"))
      (node (ref "H5") (pin "3") (pinfunction "3_3") (pintype "passive"))
      (node (ref "R11") (pin "1") (pintype "passive"))
    )
    (net (code "14") (name "/PB1") (class "Default")
      (node (ref "*1") (pin "27") (pinfunction "PB1_27") (pintype "bidirectional"))
      (node (ref "H5") (pin "4") (pinfunction "4_4") (pintype "passive"))
      (node (ref "R12") (pin "1") (pintype "passive"))
    )
    (net (code "15") (name "/PB12") (class "Default")
      (node (ref "*1") (pin "33") (pinfunction "PB12_33") (pintype "bidirectional"))
      (node (ref "U3") (pin "2") (pinfunction "INA_2") (pintype "passive"))
      (node (ref "U3") (pin "4") (pinfunction "INB_4") (pintype "passive"))
    )
    (net (code "16") (name "/PB13") (class "Default")
      (node (ref "*1") (pin "34") (pinfunction "PB13_34") (pintype "bidirectional"))
      (node (ref "U4") (pin "2") (pinfunction "INA_2") (pintype "passive"))
      (node (ref "U4") (pin "4") (pinfunction "INB_4") (pintype "passive"))
    )
    (net (code "17") (name "/PC0") (class "Default")
      (node (ref "*1") (pin "8") (pinfunction "PC0_8") (pintype "bidirectional"))
      (node (ref "C24") (pin "1") (pinfunction "1_1") (pintype "passive"))
      (node (ref "S2") (pin "1") (pinfunction "1_1") (pintype "passive"))
    )
    (net (code "18") (name "/PC1") (class "Default")
      (node (ref "*1") (pin "9") (pinfunction "PC1_9") (pintype "bidirectional"))
      (node (ref "C25") (pin "1") (pinfunction "1_1") (pintype "passive"))
      (node (ref "S3") (pin "1") (pinfunction "1_1") (pintype "passive"))
    )
    (net (code "19") (name "/PC2") (class "Default")
      (node (ref "*1") (pin "10") (pinfunction "PC2_10") (pintype "bidirectional"))
      (node (ref "C28") (pin "1") (pinfunction "1_1") (pintype "passive"))
      (node (ref "S4") (pin "1") (pinfunction "1_1") (pintype "passive"))
    )
    (net (code "20") (name "/PC3") (class "Default")
      (node (ref "*1") (pin "11") (pinfunction "PC3_11") (pintype "bidirectional"))
      (node (ref "C35") (pin "1") (pinfunction "1_1") (pintype "passive"))
      (node (ref "S5") (pin "1") (pinfunction "1_1") (pintype "passive"))
    )
    (net (code "21") (name "/PC4") (class "Default")
      (node (ref "*1") (pin "24") (pinfunction "PC4_24") (pintype "bidirectional"))
      (node (ref "H13") (pin "2") (pinfunction "2_2") (pintype "passive"))
    )
    (net (code "22") (name "/PC5") (class "Default")
      (node (ref "*1") (pin "25") (pinfunction "PC5_25") (pintype "bidirectional"))
      (node (ref "H15") (pin "2") (pinfunction "2_2") (pintype "passive"))
    )
    (net (code "23") (name "/PC12") (class "Default")
      (node (ref "*1") (pin "53") (pinfunction "PC12_53") (pintype "bidirectional"))
      (node (ref "U8") (pin "2") (pinfunction "INA_2") (pintype "passive"))
      (node (ref "U8") (pin "4") (pinfunction "INB_4") (pintype "passive"))
    )
    (net (code "24") (name "/PD2") (class "Default")
      (node (ref "*1") (pin "54") (pinfunction "PD2_54") (pintype "bidirectional"))
      (node (ref "U7") (pin "2") (pinfunction "INA_2") (pintype "passive"))
      (node (ref "U7") (pin "4") (pinfunction "INB_4") (pintype "passive"))
    )
    (net (code "25") (name "/SWCLK") (class "Default")
      (node (ref "*1") (pin "49") (pinfunction "PA14(JTCK-SWCLK)_49") (pintype "bidirectional"))
      (node (ref "*2") (pin "2") (pinfunction "D-_2") (pintype "passive"))
      (node (ref "R23") (pin "1") (pintype "passive"))
    )
    (net (code "26") (name "/SWDIO") (class "Default")
      (node (ref "*1") (pin "46") (pinfunction "PA13(JTMS-SWDIO)_46") (pintype "bidirectional"))
      (node (ref "*2") (pin "3") (pinfunction "D+_3") (pintype "passive"))
      (node (ref "R24") (pin "1") (pintype "passive"))
    )
    (net (code "27") (name "/TIM1CH1") (class "Default")
      (node (ref "*1") (pin "41") (pinfunction "PA8_41") (pintype "bidirectional"))
      (node (ref "D3") (pin "1") (pintype "passive"))
      (node (ref "H2") (pin "2") (pinfunction "2_2") (pintype "passive"))
      (node (ref "R3") (pin "1") (pintype "passive"))
    )
    (net (code "28") (name "/TIM1CH2") (class "Default")
      (node (ref "*1") (pin "42") (pinfunction "PA9_42") (pintype "bidirectional"))
      (node (ref "D4") (pin "1") (pintype "passive"))
      (node (ref "H2") (pin "3") (pinfunction "3_3") (pintype "passive"))
      (node (ref "R4") (pin "1") (pintype "passive"))
    )
    (net (code "29") (name "/TIM2CH1") (class "Default")
      (node (ref "*1") (pin "50") (pinfunction "PA15(JTDI)_50") (pintype "bidirectional"))
      (node (ref "D13") (pin "1") (pintype "passive"))
      (node (ref "H7") (pin "2") (pinfunction "2_2") (pintype "passive"))
      (node (ref "R15") (pin "1") (pintype "passive"))
    )
    (net (code "30") (name "/TIM2CH2") (class "Default")
      (node (ref "*1") (pin "55") (pinfunction "PB3(JTDO/TRACESWO)_55") (pintype "bidirectional"))
      (node (ref "D15") (pin "1") (pintype "passive"))
      (node (ref "H7") (pin "3") (pinfunction "3_3") (pintype "passive"))
      (node (ref "R16") (pin "1") (pintype "passive"))
    )
    (net (code "31") (name "/TIM3CH1") (class "Default")
      (node (ref "*1") (pin "56") (pinfunction "PB4(NJTRST)_56") (pintype "bidirectional"))
      (node (ref "D9") (pin "1") (pintype "passive"))
      (node (ref "H6") (pin "2") (pinfunction "2_2") (pintype "passive"))
      (node (ref "R13") (pin "1") (pintype "passive"))
    )
    (net (code "32") (name "/TIM3CH2") (class "Default")
      (node (ref "*1") (pin "57") (pinfunction "PB5_57") (pintype "bidirectional"))
      (node (ref "D10") (pin "1") (pintype "passive"))
      (node (ref "H6") (pin "3") (pinfunction "3_3") (pintype "passive"))
      (node (ref "R14") (pin "1") (pintype "passive"))
    )
    (net (code "33") (name "/TIM4CH1") (class "Default")
      (node (ref "*1") (pin "58") (pinfunction "PB6_58") (pintype "bidirectional"))
      (node (ref "U5") (pin "10") (pinfunction "IH2_10") (pintype "passive"))
    )
    (net (code "34") (name "/TIM4CH2") (class "Default")
      (node (ref "*1") (pin "59") (pinfunction "PB7_59") (pintype "bidirectional"))
      (node (ref "U5") (pin "5") (pinfunction "IH1_5") (pintype "passive"))
    )
    (net (code "35") (name "/TIM4CH3") (class "Default")
      (node (ref "*1") (pin "61") (pinfunction "PB8_61") (pintype "bidirectional"))
      (node (ref "U6") (pin "10") (pinfunction "IH2_10") (pintype "passive"))
    )
    (net (code "36") (name "/TIM4CH4") (class "Default")
      (node (ref "*1") (pin "62") (pinfunction "PB9_62") (pintype "bidirectional"))
      (node (ref "U6") (pin "5") (pinfunction "IH1_5") (pintype "passive"))
    )
    (net (code "37") (name "/TIM8CH1") (class "Default")
      (node (ref "*1") (pin "37") (pinfunction "PC6_37") (pintype "bidirectional"))
      (node (ref "U1") (pin "10") (pinfunction "IH2_10") (pintype "passive"))
    )
    (net (code "38") (name "/TIM8CH2") (class "Default")
      (node (ref "*1") (pin "38") (pinfunction "PC7_38") (pintype "bidirectional"))
      (node (ref "U1") (pin "5") (pinfunction "IH1_5") (pintype "passive"))
    )
    (net (code "39") (name "/TIM8CH3") (class "Default")
      (node (ref "*1") (pin "39") (pinfunction "PC8_39") (pintype "bidirectional"))
      (node (ref "U2") (pin "10") (pinfunction "IH2_10") (pintype "passive"))
    )
    (net (code "40") (name "/TIM8CH4") (class "Default")
      (node (ref "*1") (pin "40") (pinfunction "PC9_40") (pintype "bidirectional"))
      (node (ref "U2") (pin "5") (pinfunction "IH1_5") (pintype "passive"))
    )
    (net (code "41") (name "/TIM12CH1") (class "Default")
      (node (ref "*1") (pin "35") (pinfunction "PB14_35") (pintype "bidirectional"))
      (node (ref "D1") (pin "1") (pintype "passive"))
      (node (ref "H1") (pin "2") (pinfunction "2_2") (pintype "passive"))
      (node (ref "R1") (pin "1") (pintype "passive"))
    )
    (net (code "42") (name "/TIM12CH2") (class "Default")
      (node (ref "*1") (pin "36") (pinfunction "PB15_36") (pintype "bidirectional"))
      (node (ref "D2") (pin "1") (pintype "passive"))
      (node (ref "H1") (pin "3") (pinfunction "3_3") (pintype "passive"))
      (node (ref "R2") (pin "1") (pintype "passive"))
    )
    (net (code "43") (name "/UART4 TX") (class "Default")
      (node (ref "*1") (pin "14") (pinfunction "PA0-WKUP(PA0)_14") (pintype "bidirectional"))
      (node (ref "R32") (pin "2") (pintype "passive"))
    )
    (net (code "44") (name "/USART2 RX") (class "Default")
      (node (ref "*1") (pin "17") (pinfunction "PA3_17") (pintype "bidirectional"))
      (node (ref "R35") (pin "2") (pintype "passive"))
    )
    (net (code "45") (name "/USART2 TX") (class "Default")
      (node (ref "*1") (pin "16") (pinfunction "PA2_16") (pintype "bidirectional"))
      (node (ref "R36") (pin "2") (pintype "passive"))
    )
    (net (code "46") (name "/USART3 RX") (class "Default")
      (node (ref "*1") (pin "52") (pinfunction "PC11_52") (pintype "bidirectional"))
      (node (ref "R37") (pin "2") (pintype "passive"))
    )
    (net (code "47") (name "/USART3 TX") (class "Default")
      (node (ref "*1") (pin "51") (pinfunction "PC10_51") (pintype "bidirectional"))
      (node (ref "R38") (pin "2") (pintype "passive"))
    )
    (net (code "48") (name "/USRT4 RX") (class "Default")
      (node (ref "*1") (pin "15") (pinfunction "PA1_15") (pintype "bidirectional"))
      (node (ref "R31") (pin "2") (pintype "passive"))
    )
    (net (code "49") (name "GND") (class "Default")
      (node (ref "*1") (pin "12") (pinfunction "VSSA_12") (pintype "power_in"))
      (node (ref "*1") (pin "18") (pinfunction "VSS_18") (pintype "power_in"))
      (node (ref "*1") (pin "28") (pinfunction "PB2-BOOT1(PB2)_28") (pintype "bidirectional"))
      (node (ref "*1") (pin "60") (pinfunction "BOOT0_60") (pintype "input"))
      (node (ref "*1") (pin "63") (pinfunction "VSS_63") (pintype "power_in"))
      (node (ref "*2") (pin "4") (pinfunction "ID_4") (pintype "passive"))
      (node (ref "*2") (pin "5") (pinfunction "GND_5") (pintype "passive"))
      (node (ref "*2") (pin "6") (pinfunction "SHELL_6") (pintype "passive"))
      (node (ref "*3") (pin "1") (pinfunction "1_1") (pintype "passive"))
      (node (ref "C1") (pin "2") (pinfunction "2_2") (pintype "passive"))
      (node (ref "C10") (pin "1") (pinfunction "1_1") (pintype "passive"))
      (node (ref "C11") (pin "1") (pinfunction "1_1") (pintype "passive"))
      (node (ref "C12") (pin "1") (pinfunction "1_1") (pintype "passive"))
      (node (ref "C13") (pin "1") (pinfunction "1_1") (pintype "passive"))
      (node (ref "C14") (pin "1") (pinfunction "1_1") (pintype "passive"))
      (node (ref "C15") (pin "1") (pinfunction "1_1") (pintype "passive"))
      (node (ref "C16") (pin "1") (pinfunction "1_1") (pintype "passive"))
      (node (ref "C17") (pin "1") (pinfunction "1_1") (pintype "passive"))
      (node (ref "C18") (pin "1") (pinfunction "1_1") (pintype "passive"))
      (node (ref "C19") (pin "1") (pinfunction "1_1") (pintype "passive"))
      (node (ref "C2") (pin "2") (pinfunction "2_2") (pintype "passive"))
      (node (ref "C20") (pin "1") (pinfunction "1_1") (pintype "passive"))
      (node (ref "C21") (pin "1") (pinfunction "1_1") (pintype "passive"))
      (node (ref "C22") (pin "1") (pinfunction "1_1") (pintype "passive"))
      (node (ref "C23") (pin "1") (pinfunction "1_1") (pintype "passive"))
      (node (ref "C24") (pin "2") (pinfunction "2_2") (pintype "passive"))
      (node (ref "C25") (pin "2") (pinfunction "2_2") (pintype "passive"))
      (node (ref "C26") (pin "1") (pinfunction "1_1") (pintype "passive"))
      (node (ref "C27") (pin "2") (pinfunction "2_2") (pintype "passive"))
      (node (ref "C28") (pin "2") (pinfunction "2_2") (pintype "passive"))
      (node (ref "C29") (pin "2") (pinfunction "2_2") (pintype "passive"))
      (node (ref "C3") (pin "2") (pinfunction "2_2") (pintype "passive"))
      (node (ref "C30") (pin "2") (pinfunction "2_2") (pintype "passive"))
      (node (ref "C31") (pin "2") (pinfunction "2_2") (pintype "passive"))
      (node (ref "C32") (pin "2") (pinfunction "2_2") (pintype "passive"))
      (node (ref "C33") (pin "2") (pinfunction "2_2") (pintype "passive"))
      (node (ref "C34") (pin "2") (pinfunction "2_2") (pintype "passive"))
      (node (ref "C35") (pin "2") (pinfunction "2_2") (pintype "passive"))
      (node (ref "C36") (pin "2") (pinfunction "2_2") (pintype "passive"))
      (node (ref "C37") (pin "2") (pinfunction "2_2") (pintype "passive"))
      (node (ref "C38") (pin "2") (pinfunction "2_2") (pintype "passive"))
      (node (ref "C39") (pin "2") (pinfunction "2_2") (pintype "passive"))
      (node (ref "C4") (pin "2") (pinfunction "2_2") (pintype "passive"))
      (node (ref "C41") (pin "1") (pinfunction "1_1") (pintype "passive"))
      (node (ref "C42") (pin "1") (pinfunction "1_1") (pintype "passive"))
      (node (ref "C43") (pin "1") (pinfunction "1_1") (pintype "passive"))
      (node (ref "C44") (pin "1") (pinfunction "1_1") (pintype "passive"))
      (node (ref "C45") (pin "1") (pinfunction "1_1") (pintype "passive"))
      (node (ref "C46") (pin "1") (pinfunction "1_1") (pintype "passive"))
      (node (ref "C47") (pin "2") (pinfunction "2_2") (pintype "passive"))
      (node (ref "C48") (pin "2") (pinfunction "2_2") (pintype "passive"))
      (node (ref "C5") (pin "2") (pinfunction "2_2") (pintype "passive"))
      (node (ref "C6") (pin "2") (pinfunction "2_2") (pintype "passive"))
      (node (ref "C7") (pin "1") (pinfunction "1_1") (pintype "passive"))
      (node (ref "C8") (pin "1") (pinfunction "1_1") (pintype "passive"))
      (node (ref "C9") (pin "1") (pinfunction "1_1") (pintype "passive"))
      (node (ref "D1") (pin "2") (pintype "passive"))
      (node (ref "D10") (pin "2") (pintype "passive"))
      (node (ref "D13") (pin "2") (pintype "passive"))
      (node (ref "D15") (pin "2") (pintype "passive"))
      (node (ref "D17") (pin "2") (pintype "passive"))
      (node (ref "D18") (pin "2") (pintype "passive"))
      (node (ref "D19") (pin "2") (pintype "passive"))
      (node (ref "D2") (pin "2") (pintype "passive"))
      (node (ref "D3") (pin "2") (pintype "passive"))
      (node (ref "D4") (pin "2") (pintype "passive"))
      (node (ref "D9") (pin "2") (pintype "passive"))
      (node (ref "H1") (pin "4") (pinfunction "4_4") (pintype "passive"))
      (node (ref "H11") (pin "2") (pinfunction "2_2") (pintype "passive"))
      (node (ref "H13") (pin "3") (pinfunction "3_3") (pintype "passive"))
      (node (ref "H14") (pin "2") (pinfunction "2_2") (pintype "passive"))
      (node (ref "H15") (pin "3") (pinfunction "3_3") (pintype "passive"))
      (node (ref "H16") (pin "2") (pinfunction "2_2") (pintype "passive"))
      (node (ref "H17") (pin "2") (pinfunction "2_2") (pintype "passive"))
      (node (ref "H2") (pin "4") (pinfunction "4_4") (pintype "passive"))
      (node (ref "H5") (pin "1") (pinfunction "1_1") (pintype "passive"))
      (node (ref "H6") (pin "4") (pinfunction "4_4") (pintype "passive"))
      (node (ref "H7") (pin "4") (pinfunction "4_4") (pintype "passive"))
      (node (ref "P1") (pin "8") (pinfunction "8_8") (pintype "passive"))
      (node (ref "Q？1") (pin "1") (pinfunction "A_1") (pintype "passive"))
      (node (ref "R21") (pin "1") (pintype "passive"))
      (node (ref "R29") (pin "1") (pintype "passive"))
      (node (ref "S1") (pin "2") (pinfunction "2_2") (pintype "passive"))
      (node (ref "S2") (pin "2") (pinfunction "2_2") (pintype "passive"))
      (node (ref "S3") (pin "2") (pinfunction "2_2") (pintype "passive"))
      (node (ref "S4") (pin "2") (pinfunction "2_2") (pintype "passive"))
      (node (ref "S5") (pin "2") (pinfunction "2_2") (pintype "passive"))
      (node (ref "U1") (pin "14") (pinfunction "SL2_14") (pintype "passive"))
      (node (ref "U1") (pin "2") (pinfunction "SL1_2") (pintype "passive"))
      (node (ref "U1") (pin "9") (pinfunction "GND_9") (pintype "passive"))
      (node (ref "U10") (pin "1") (pinfunction "GND_1") (pintype "passive"))
      (node (ref "U11") (pin "2") (pinfunction "GND_2") (pintype "passive"))
      (node (ref "U11") (pin "8") (pinfunction "~{CS}_8") (pintype "passive"))
      (node (ref "U2") (pin "14") (pinfunction "SL2_14") (pintype "passive"))
      (node (ref "U2") (pin "2") (pinfunction "SL1_2") (pintype "passive"))
      (node (ref "U2") (pin "9") (pinfunction "GND_9") (pintype "passive"))
      (node (ref "U3") (pin "3") (pinfunction "GND_3") (pintype "passive"))
      (node (ref "U4") (pin "3") (pinfunction "GND_3") (pintype "passive"))
      (node (ref "U5") (pin "14") (pinfunction "SL2_14") (pintype "passive"))
      (node (ref "U5") (pin "2") (pinfunction "SL1_2") (pintype "passive"))
      (node (ref "U5") (pin "9") (pinfunction "GND_9") (pintype "passive"))
      (node (ref "U6") (pin "14") (pinfunction "SL2_14") (pintype "passive"))
      (node (ref "U6") (pin "2") (pinfunction "SL1_2") (pintype "passive"))
      (node (ref "U6") (pin "9") (pinfunction "GND_9") (pintype "passive"))
      (node (ref "U7") (pin "3") (pinfunction "GND_3") (pintype "passive"))
      (node (ref "U8") (pin "3") (pinfunction "GND_3") (pintype "passive"))
      (node (ref "U9") (pin "0") (pinfunction "GND_0") (pintype "passive"))
      (node (ref "U9") (pin "6") (pinfunction "GND_6") (pintype "passive"))
    )
    (net (code "50") (name "Net-(*1A-NRST)") (class "Default")
      (node (ref "*1") (pin "7") (pinfunction "NRST_7") (pintype "bidirectional"))
      (node (ref "C21") (pin "2") (pinfunction "2_2") (pintype "passive"))
      (node (ref "S1") (pin "1") (pinfunction "1_1") (pintype "passive"))
    )
    (net (code "51") (name "Net-(*1A-PH0-OSC_IN(PH0))") (class "Default")
      (node (ref "*1") (pin "5") (pinfunction "PH0-OSC_IN(PH0)_5") (pintype "bidirectional"))
      (node (ref "C5") (pin "1") (pinfunction "1_1") (pintype "passive"))
      (node (ref "Y1") (pin "2") (pinfunction "OSC2_2") (pintype "passive"))
    )
    (net (code "52") (name "Net-(*1A-PH1-OSC_OUT(PH1))") (class "Default")
      (node (ref "*1") (pin "6") (pinfunction "PH1-OSC_OUT(PH1)_6") (pintype "bidirectional"))
      (node (ref "C6") (pin "1") (pinfunction "1_1") (pintype "passive"))
      (node (ref "Y1") (pin "1") (pinfunction "OSC1_1") (pintype "passive"))
    )
    (net (code "53") (name "Net-(*1A-VCAP_1)") (class "Default")
      (node (ref "*1") (pin "31") (pinfunction "VCAP_1_31") (pintype "power_in"))
      (node (ref "C23") (pin "2") (pinfunction "2_2") (pintype "passive"))
    )
    (net (code "54") (name "Net-(*1A-VCAP_2)") (class "Default")
      (node (ref "*1") (pin "47") (pinfunction "VCAP_2_47") (pintype "power_in"))
      (node (ref "C22") (pin "2") (pinfunction "2_2") (pintype "passive"))
    )
    (net (code "55") (name "Net-(B1-V-)") (class "Default")
      (node (ref "B1") (pin "0") (pinfunction "V-_0") (pintype "power_in"))
      (node (ref "Q1") (pin "3") (pinfunction "c_3") (pintype "passive"))
    )
    (net (code "56") (name "Net-(D5-Pad2)") (class "Default")
      (node (ref "D5") (pin "2") (pintype "passive"))
      (node (ref "R7") (pin "1") (pintype "passive"))
    )
    (net (code "57") (name "Net-(D6-Pad2)") (class "Default")
      (node (ref "D6") (pin "2") (pintype "passive"))
      (node (ref "R8") (pin "1") (pintype "passive"))
    )
    (net (code "58") (name "Net-(D7-Pad2)") (class "Default")
      (node (ref "D7") (pin "2") (pintype "passive"))
      (node (ref "R9") (pin "1") (pintype "passive"))
    )
    (net (code "59") (name "Net-(D8-Pad2)") (class "Default")
      (node (ref "D8") (pin "2") (pintype "passive"))
      (node (ref "R10") (pin "1") (pintype "passive"))
    )
    (net (code "60") (name "Net-(D11-Pad2)") (class "Default")
      (node (ref "D11") (pin "2") (pintype "passive"))
      (node (ref "R17") (pin "1") (pintype "passive"))
    )
    (net (code "61") (name "Net-(D12-Pad2)") (class "Default")
      (node (ref "D12") (pin "2") (pintype "passive"))
      (node (ref "R18") (pin "1") (pintype "passive"))
    )
    (net (code "62") (name "Net-(D14-Pad2)") (class "Default")
      (node (ref "D14") (pin "2") (pintype "passive"))
      (node (ref "R19") (pin "1") (pintype "passive"))
    )
    (net (code "63") (name "Net-(D16-Pad2)") (class "Default")
      (node (ref "D16") (pin "2") (pintype "passive"))
      (node (ref "R20") (pin "1") (pintype "passive"))
    )
    (net (code "64") (name "Net-(D17-Pad1)") (class "Default")
      (node (ref "D17") (pin "1") (pintype "passive"))
      (node (ref "R26") (pin "2") (pintype "passive"))
    )
    (net (code "65") (name "Net-(D18-Pad1)") (class "Default")
      (node (ref "D18") (pin "1") (pintype "passive"))
      (node (ref "R28") (pin "2") (pintype "passive"))
    )
    (net (code "66") (name "Net-(D19-Pad1)") (class "Default")
      (node (ref "D19") (pin "1") (pintype "passive"))
      (node (ref "R27") (pin "2") (pintype "passive"))
    )
    (net (code "67") (name "Net-(D20-Pad1)") (class "Default")
      (node (ref "D20") (pin "1") (pintype "passive"))
      (node (ref "R30") (pin "2") (pintype "passive"))
    )
    (net (code "68") (name "Net-(D21-OUT-Pad1)") (class "Default")
      (node (ref "D21") (pin "1") (pinfunction "OUT_1") (pintype "passive"))
      (node (ref "R33") (pin "7") (pintype "passive"))
    )
    (net (code "69") (name "Net-(D21-OUT-Pad3)") (class "Default")
      (node (ref "D21") (pin "3") (pinfunction "OUT_3") (pintype "passive"))
      (node (ref "R33") (pin "3") (pintype "passive"))
    )
    (net (code "70") (name "Net-(D21-OUT-Pad4)") (class "Default")
      (node (ref "D21") (pin "4") (pinfunction "OUT_4") (pintype "passive"))
      (node (ref "R33") (pin "5") (pintype "passive"))
    )
    (net (code "71") (name "Net-(H14-Pad3)") (class "Default")
      (node (ref "H14") (pin "3") (pinfunction "3_3") (pintype "passive"))
      (node (ref "R31") (pin "1") (pintype "passive"))
    )
    (net (code "72") (name "Net-(H14-Pad4)") (class "Default")
      (node (ref "H14") (pin "4") (pinfunction "4_4") (pintype "passive"))
      (node (ref "R32") (pin "1") (pintype "passive"))
    )
    (net (code "73") (name "Net-(H16-Pad3)") (class "Default")
      (node (ref "H16") (pin "3") (pinfunction "3_3") (pintype "passive"))
      (node (ref "R35") (pin "1") (pintype "passive"))
    )
    (net (code "74") (name "Net-(H16-Pad4)") (class "Default")
      (node (ref "H16") (pin "4") (pinfunction "4_4") (pintype "passive"))
      (node (ref "R36") (pin "1") (pintype "passive"))
    )
    (net (code "75") (name "Net-(H17-Pad3)") (class "Default")
      (node (ref "H17") (pin "3") (pinfunction "3_3") (pintype "passive"))
      (node (ref "R37") (pin "1") (pintype "passive"))
    )
    (net (code "76") (name "Net-(H17-Pad4)") (class "Default")
      (node (ref "H17") (pin "4") (pinfunction "4_4") (pintype "passive"))
      (node (ref "R38") (pin "1") (pintype "passive"))
    )
    (net (code "77") (name "Net-(Q1-b)") (class "Default")
      (node (ref "Q1") (pin "1") (pinfunction "b_1") (pintype "passive"))
      (node (ref "R25") (pin "2") (pintype "passive"))
    )
    (net (code "78") (name "Net-(Q1-e)") (class "Default")
      (node (ref "Q1") (pin "2") (pinfunction "e_2") (pintype "passive"))
      (node (ref "R29") (pin "2") (pintype "passive"))
    )
    (net (code "79") (name "Net-(Q？1-K)") (class "Default")
      (node (ref "C40") (pin "2") (pinfunction "2_2") (pintype "passive"))
      (node (ref "H10") (pin "1") (pinfunction "1_1") (pintype "passive"))
      (node (ref "Q？1") (pin "2") (pinfunction "K_2") (pintype "passive"))
      (node (ref "U9") (pin "8") (pinfunction "PH_8") (pintype "passive"))
    )
    (net (code "80") (name "Net-(U1-DL1)") (class "Default")
      (node (ref "H3") (pin "1") (pinfunction "1_1") (pintype "passive"))
      (node (ref "U1") (pin "18") (pinfunction "DL1_18") (pintype "passive"))
      (node (ref "U1") (pin "7") (pinfunction "SH1_7") (pintype "passive"))
    )
    (net (code "81") (name "Net-(U1-DL2)") (class "Default")
      (node (ref "H3") (pin "2") (pinfunction "2_2") (pintype "passive"))
      (node (ref "U1") (pin "12") (pinfunction "SH2_12") (pintype "passive"))
      (node (ref "U1") (pin "16") (pinfunction "DL2_16") (pintype "passive"))
    )
    (net (code "82") (name "Net-(U1-IL1)") (class "Default")
      (node (ref "U1") (pin "3") (pinfunction "IL1_3") (pintype "passive"))
      (node (ref "U3") (pin "7") (pinfunction "OUTA_7") (pintype "passive"))
    )
    (net (code "83") (name "Net-(U1-IL2)") (class "Default")
      (node (ref "U1") (pin "13") (pinfunction "IL2_13") (pintype "passive"))
      (node (ref "U3") (pin "5") (pinfunction "OUTB_5") (pintype "passive"))
    )
    (net (code "84") (name "Net-(U1-ST1)") (class "Default")
      (node (ref "R7") (pin "2") (pintype "passive"))
      (node (ref "U1") (pin "6") (pinfunction "ST1_6") (pintype "passive"))
    )
    (net (code "85") (name "Net-(U1-ST2)") (class "Default")
      (node (ref "R9") (pin "2") (pintype "passive"))
      (node (ref "U1") (pin "11") (pinfunction "ST2_11") (pintype "passive"))
    )
    (net (code "86") (name "Net-(U2-DL1)") (class "Default")
      (node (ref "H4") (pin "1") (pinfunction "1_1") (pintype "passive"))
      (node (ref "U2") (pin "18") (pinfunction "DL1_18") (pintype "passive"))
      (node (ref "U2") (pin "7") (pinfunction "SH1_7") (pintype "passive"))
    )
    (net (code "87") (name "Net-(U2-DL2)") (class "Default")
      (node (ref "H4") (pin "2") (pinfunction "2_2") (pintype "passive"))
      (node (ref "U2") (pin "12") (pinfunction "SH2_12") (pintype "passive"))
      (node (ref "U2") (pin "16") (pinfunction "DL2_16") (pintype "passive"))
    )
    (net (code "88") (name "Net-(U2-IL1)") (class "Default")
      (node (ref "U2") (pin "3") (pinfunction "IL1_3") (pintype "passive"))
      (node (ref "U4") (pin "7") (pinfunction "OUTA_7") (pintype "passive"))
    )
    (net (code "89") (name "Net-(U2-IL2)") (class "Default")
      (node (ref "U2") (pin "13") (pinfunction "IL2_13") (pintype "passive"))
      (node (ref "U4") (pin "5") (pinfunction "OUTB_5") (pintype "passive"))
    )
    (net (code "90") (name "Net-(U2-ST1)") (class "Default")
      (node (ref "R8") (pin "2") (pintype "passive"))
      (node (ref "U2") (pin "6") (pinfunction "ST1_6") (pintype "passive"))
    )
    (net (code "91") (name "Net-(U2-ST2)") (class "Default")
      (node (ref "R10") (pin "2") (pintype "passive"))
      (node (ref "U2") (pin "11") (pinfunction "ST2_11") (pintype "passive"))
    )
    (net (code "92") (name "Net-(U5-DL1)") (class "Default")
      (node (ref "H8") (pin "1") (pinfunction "1_1") (pintype "passive"))
      (node (ref "U5") (pin "18") (pinfunction "DL1_18") (pintype "passive"))
      (node (ref "U5") (pin "7") (pinfunction "SH1_7") (pintype "passive"))
    )
    (net (code "93") (name "Net-(U5-DL2)") (class "Default")
      (node (ref "H8") (pin "2") (pinfunction "2_2") (pintype "passive"))
      (node (ref "U5") (pin "12") (pinfunction "SH2_12") (pintype "passive"))
      (node (ref "U5") (pin "16") (pinfunction "DL2_16") (pintype "passive"))
    )
    (net (code "94") (name "Net-(U5-IL1)") (class "Default")
      (node (ref "U5") (pin "3") (pinfunction "IL1_3") (pintype "passive"))
      (node (ref "U7") (pin "7") (pinfunction "OUTA_7") (pintype "passive"))
    )
    (net (code "95") (name "Net-(U5-IL2)") (class "Default")
      (node (ref "U5") (pin "13") (pinfunction "IL2_13") (pintype "passive"))
      (node (ref "U7") (pin "5") (pinfunction "OUTB_5") (pintype "passive"))
    )
    (net (code "96") (name "Net-(U5-ST1)") (class "Default")
      (node (ref "R17") (pin "2") (pintype "passive"))
      (node (ref "U5") (pin "6") (pinfunction "ST1_6") (pintype "passive"))
    )
    (net (code "97") (name "Net-(U5-ST2)") (class "Default")
      (node (ref "R19") (pin "2") (pintype "passive"))
      (node (ref "U5") (pin "11") (pinfunction "ST2_11") (pintype "passive"))
    )
    (net (code "98") (name "Net-(U6-DL1)") (class "Default")
      (node (ref "H9") (pin "1") (pinfunction "1_1") (pintype "passive"))
      (node (ref "U6") (pin "18") (pinfunction "DL1_18") (pintype "passive"))
      (node (ref "U6") (pin "7") (pinfunction "SH1_7") (pintype "passive"))
    )
    (net (code "99") (name "Net-(U6-DL2)") (class "Default")
      (node (ref "H9") (pin "2") (pinfunction "2_2") (pintype "passive"))
      (node (ref "U6") (pin "12") (pinfunction "SH2_12") (pintype "passive"))
      (node (ref "U6") (pin "16") (pinfunction "DL2_16") (pintype "passive"))
    )
    (net (code "100") (name "Net-(U6-IL1)") (class "Default")
      (node (ref "U6") (pin "3") (pinfunction "IL1_3") (pintype "passive"))
      (node (ref "U8") (pin "7") (pinfunction "OUTA_7") (pintype "passive"))
    )
    (net (code "101") (name "Net-(U6-IL2)") (class "Default")
      (node (ref "U6") (pin "13") (pinfunction "IL2_13") (pintype "passive"))
      (node (ref "U8") (pin "5") (pinfunction "OUTB_5") (pintype "passive"))
    )
    (net (code "102") (name "Net-(U6-ST1)") (class "Default")
      (node (ref "R18") (pin "2") (pintype "passive"))
      (node (ref "U6") (pin "6") (pinfunction "ST1_6") (pintype "passive"))
    )
    (net (code "103") (name "Net-(U6-ST2)") (class "Default")
      (node (ref "R20") (pin "2") (pintype "passive"))
      (node (ref "U6") (pin "11") (pinfunction "ST2_11") (pintype "passive"))
    )
    (net (code "104") (name "Net-(U9-BOOT)") (class "Default")
      (node (ref "C40") (pin "1") (pinfunction "1_1") (pintype "passive"))
      (node (ref "U9") (pin "1") (pinfunction "BOOT_1") (pintype "passive"))
    )
    (net (code "105") (name "Net-(U9-VSENSE)") (class "Default")
      (node (ref "R21") (pin "2") (pintype "passive"))
      (node (ref "R22") (pin "1") (pintype "passive"))
      (node (ref "U9") (pin "4") (pinfunction "VSENSE_4") (pintype "passive"))
    )
    (net (code "106") (name "VCC") (class "Default")
      (node (ref "H11") (pin "1") (pinfunction "1_1") (pintype "passive"))
      (node (ref "S6") (pin "1") (pinfunction "1_1") (pintype "passive"))
      (node (ref "S6") (pin "2") (pinfunction "2_2") (pintype "passive"))
    )
    (net (code "107") (name "VCC-3.3V") (class "Default")
      (node (ref "*1") (pin "1") (pinfunction "VBAT_1") (pintype "power_in"))
      (node (ref "*1") (pin "13") (pinfunction "VDDA_13") (pintype "power_in"))
      (node (ref "*1") (pin "19") (pinfunction "VDD_19") (pintype "power_in"))
      (node (ref "*1") (pin "32") (pinfunction "VDD_32") (pintype "power_in"))
      (node (ref "*1") (pin "48") (pinfunction "VDD_48") (pintype "power_in"))
      (node (ref "*1") (pin "64") (pinfunction "VDD_64") (pintype "power_in"))
      (node (ref "*2") (pin "1") (pinfunction "UV_1") (pintype "passive"))
      (node (ref "C26") (pin "2") (pinfunction "2_2") (pintype "passive"))
      (node (ref "C27") (pin "1") (pinfunction "1_1") (pintype "passive"))
      (node (ref "C29") (pin "1") (pinfunction "1_1") (pintype "passive"))
      (node (ref "C30") (pin "1") (pinfunction "1_1") (pintype "passive"))
      (node (ref "C36") (pin "1") (pinfunction "1_1") (pintype "passive"))
      (node (ref "C37") (pin "1") (pinfunction "1_1") (pintype "passive"))
      (node (ref "C42") (pin "2") (pinfunction "2_2") (pintype "passive"))
      (node (ref "C43") (pin "2") (pinfunction "2_2") (pintype "passive"))
      (node (ref "C44") (pin "2") (pinfunction "2_2") (pintype "passive"))
      (node (ref "C47") (pin "1") (pinfunction "1_1") (pintype "passive"))
      (node (ref "C48") (pin "1") (pinfunction "1_1") (pintype "passive"))
      (node (ref "D21") (pin "2") (pinfunction "OUT_2") (pintype "passive"))
      (node (ref "H5") (pin "2") (pinfunction "2_2") (pintype "passive"))
      (node (ref "P1") (pin "9") (pinfunction "9_9") (pintype "passive"))
      (node (ref "R11") (pin "2") (pintype "passive"))
      (node (ref "R12") (pin "2") (pintype "passive"))
      (node (ref "R23") (pin "2") (pintype "passive"))
      (node (ref "R24") (pin "2") (pintype "passive"))
      (node (ref "R27") (pin "1") (pintype "passive"))
      (node (ref "R30") (pin "1") (pintype "passive"))
      (node (ref "R5") (pin "2") (pintype "passive"))
      (node (ref "R6") (pin "2") (pintype "passive"))
      (node (ref "U10") (pin "2") (pinfunction "3.3_2") (pintype "passive"))
      (node (ref "U11") (pin "3") (pinfunction "Vcc_3") (pintype "passive"))
    )
    (net (code "108") (name "VCC-5.0V") (class "Default")
      (node (ref "*3") (pin "2") (pinfunction "2_2") (pintype "passive"))
      (node (ref "B1") (pin "1") (pinfunction "V+_1") (pintype "power_in"))
      (node (ref "C1") (pin "1") (pinfunction "1_1") (pintype "passive"))
      (node (ref "C2") (pin "1") (pinfunction "1_1") (pintype "passive"))
      (node (ref "C3") (pin "1") (pinfunction "1_1") (pintype "passive"))
      (node (ref "C31") (pin "1") (pinfunction "1_1") (pintype "passive"))
      (node (ref "C32") (pin "1") (pinfunction "1_1") (pintype "passive"))
      (node (ref "C33") (pin "1") (pinfunction "1_1") (pintype "passive"))
      (node (ref "C34") (pin "1") (pinfunction "1_1") (pintype "passive"))
      (node (ref "C4") (pin "1") (pinfunction "1_1") (pintype "passive"))
      (node (ref "C41") (pin "2") (pinfunction "2_2") (pintype "passive"))
      (node (ref "C45") (pin "2") (pinfunction "2_2") (pintype "passive"))
      (node (ref "C46") (pin "2") (pinfunction "2_2") (pintype "passive"))
      (node (ref "D11") (pin "1") (pintype "passive"))
      (node (ref "D12") (pin "1") (pintype "passive"))
      (node (ref "D14") (pin "1") (pintype "passive"))
      (node (ref "D16") (pin "1") (pintype "passive"))
      (node (ref "D5") (pin "1") (pintype "passive"))
      (node (ref "D6") (pin "1") (pintype "passive"))
      (node (ref "D7") (pin "1") (pintype "passive"))
      (node (ref "D8") (pin "1") (pintype "passive"))
      (node (ref "H1") (pin "1") (pinfunction "1_1") (pintype "passive"))
      (node (ref "H10") (pin "2") (pinfunction "2_2") (pintype "passive"))
      (node (ref "H13") (pin "1") (pinfunction "1_1") (pintype "passive"))
      (node (ref "H14") (pin "1") (pinfunction "1_1") (pintype "passive"))
      (node (ref "H15") (pin "1") (pinfunction "1_1") (pintype "passive"))
      (node (ref "H16") (pin "1") (pinfunction "1_1") (pintype "passive"))
      (node (ref "H17") (pin "1") (pinfunction "1_1") (pintype "passive"))
      (node (ref "H2") (pin "1") (pinfunction "1_1") (pintype "passive"))
      (node (ref "H6") (pin "1") (pinfunction "1_1") (pintype "passive"))
      (node (ref "H7") (pin "1") (pinfunction "1_1") (pintype "passive"))
      (node (ref "R1") (pin "2") (pintype "passive"))
      (node (ref "R13") (pin "2") (pintype "passive"))
      (node (ref "R14") (pin "2") (pintype "passive"))
      (node (ref "R15") (pin "2") (pintype "passive"))
      (node (ref "R16") (pin "2") (pintype "passive"))
      (node (ref "R2") (pin "2") (pintype "passive"))
      (node (ref "R22") (pin "2") (pintype "passive"))
      (node (ref "R28") (pin "1") (pintype "passive"))
      (node (ref "R3") (pin "2") (pintype "passive"))
      (node (ref "R4") (pin "2") (pintype "passive"))
      (node (ref "U10") (pin "3") (pinfunction "3_3") (pintype "passive"))
      (node (ref "U3") (pin "6") (pinfunction "VS_6") (pintype "passive"))
      (node (ref "U4") (pin "6") (pinfunction "VS_6") (pintype "passive"))
      (node (ref "U7") (pin "6") (pinfunction "VS_6") (pintype "passive"))
      (node (ref "U8") (pin "6") (pinfunction "VS_6") (pintype "passive"))
    )
    (net (code "109") (name "VCC-24V") (class "Default")
      (node (ref "C10") (pin "2") (pinfunction "2_2") (pintype "passive"))
      (node (ref "C11") (pin "2") (pinfunction "2_2") (pintype "passive"))
      (node (ref "C12") (pin "2") (pinfunction "2_2") (pintype "passive"))
      (node (ref "C13") (pin "2") (pinfunction "2_2") (pintype "passive"))
      (node (ref "C14") (pin "2") (pinfunction "2_2") (pintype "passive"))
      (node (ref "C15") (pin "2") (pinfunction "2_2") (pintype "passive"))
      (node (ref "C16") (pin "2") (pinfunction "2_2") (pintype "passive"))
      (node (ref "C17") (pin "2") (pinfunction "2_2") (pintype "passive"))
      (node (ref "C18") (pin "2") (pinfunction "2_2") (pintype "passive"))
      (node (ref "C19") (pin "2") (pinfunction "2_2") (pintype "passive"))
      (node (ref "C20") (pin "2") (pinfunction "2_2") (pintype "passive"))
      (node (ref "C38") (pin "1") (pinfunction "1_1") (pintype "passive"))
      (node (ref "C39") (pin "1") (pinfunction "1_1") (pintype "passive"))
      (node (ref "C7") (pin "2") (pinfunction "2_2") (pintype "passive"))
      (node (ref "C8") (pin "2") (pinfunction "2_2") (pintype "passive"))
      (node (ref "C9") (pin "2") (pinfunction "2_2") (pintype "passive"))
      (node (ref "R26") (pin "1") (pintype "passive"))
      (node (ref "S6") (pin "3") (pinfunction "3_3") (pintype "passive"))
      (node (ref "U1") (pin "17") (pinfunction "DHVS_17") (pintype "passive"))
      (node (ref "U1") (pin "8") (pinfunction "DHVS_8") (pintype "passive"))
      (node (ref "U2") (pin "17") (pinfunction "DHVS_17") (pintype "passive"))
      (node (ref "U2") (pin "8") (pinfunction "DHVS_8") (pintype "passive"))
      (node (ref "U5") (pin "17") (pinfunction "DHVS_17") (pintype "passive"))
      (node (ref "U5") (pin "8") (pinfunction "DHVS_8") (pintype "passive"))
      (node (ref "U6") (pin "17") (pinfunction "DHVS_17") (pintype "passive"))
      (node (ref "U6") (pin "8") (pinfunction "DHVS_8") (pintype "passive"))
      (node (ref "U9") (pin "7") (pinfunction "VIN_7") (pintype "passive"))
    )
    (net (code "110") (name "unconnected-(*1A-PA10-Pad43)") (class "Default")
      (node (ref "*1") (pin "43") (pinfunction "PA10_43") (pintype "bidirectional"))
    )
    (net (code "111") (name "unconnected-(*1A-PC14-OSC32_IN(PC14)-Pad3)") (class "Default")
      (node (ref "*1") (pin "3") (pinfunction "PC14-OSC32_IN(PC14)_3") (pintype "bidirectional+no_connect"))
    )
    (net (code "112") (name "unconnected-(*1A-PC15-OSC32_OUT(PC15)-Pad4)") (class "Default")
      (node (ref "*1") (pin "4") (pinfunction "PC15-OSC32_OUT(PC15)_4") (pintype "bidirectional+no_connect"))
    )
    (net (code "113") (name "unconnected-(P1-Pad2)") (class "Default")
      (node (ref "P1") (pin "2") (pinfunction "2_2") (pintype "passive"))
    )
    (net (code "114") (name "unconnected-(P1-Pad3)") (class "Default")
      (node (ref "P1") (pin "3") (pinfunction "3_3") (pintype "passive"))
    )
    (net (code "115") (name "unconnected-(P1-Pad4)") (class "Default")
      (node (ref "P1") (pin "4") (pinfunction "4_4") (pintype "passive"))
    )
    (net (code "116") (name "unconnected-(P1-Pad5)") (class "Default")
      (node (ref "P1") (pin "5") (pinfunction "5_5") (pintype "passive"))
    )
    (net (code "117") (name "unconnected-(R33-Pad1)") (class "Default")
      (node (ref "R33") (pin "1") (pintype "passive"))
    )
    (net (code "118") (name "unconnected-(R33-Pad2)") (class "Default")
      (node (ref "R33") (pin "2") (pintype "passive"))
    )
    (net (code "119") (name "unconnected-(U1-NC-Pad1)") (class "Default")
      (node (ref "U1") (pin "1") (pinfunction "NC_1") (pintype "passive+no_connect"))
    )
    (net (code "120") (name "unconnected-(U1-NC-Pad4)") (class "Default")
      (node (ref "U1") (pin "4") (pinfunction "NC_4") (pintype "passive+no_connect"))
    )
    (net (code "121") (name "unconnected-(U1-NC-Pad15)") (class "Default")
      (node (ref "U1") (pin "15") (pinfunction "NC_15") (pintype "passive+no_connect"))
    )
    (net (code "122") (name "unconnected-(U2-NC-Pad1)") (class "Default")
      (node (ref "U2") (pin "1") (pinfunction "NC_1") (pintype "passive+no_connect"))
    )
    (net (code "123") (name "unconnected-(U2-NC-Pad4)") (class "Default")
      (node (ref "U2") (pin "4") (pinfunction "NC_4") (pintype "passive+no_connect"))
    )
    (net (code "124") (name "unconnected-(U2-NC-Pad15)") (class "Default")
      (node (ref "U2") (pin "15") (pinfunction "NC_15") (pintype "passive+no_connect"))
    )
    (net (code "125") (name "unconnected-(U3-NC-Pad1)") (class "Default")
      (node (ref "U3") (pin "1") (pinfunction "NC_1") (pintype "passive+no_connect"))
    )
    (net (code "126") (name "unconnected-(U3-NC-Pad8)") (class "Default")
      (node (ref "U3") (pin "8") (pinfunction "NC_8") (pintype "passive+no_connect"))
    )
    (net (code "127") (name "unconnected-(U4-NC-Pad1)") (class "Default")
      (node (ref "U4") (pin "1") (pinfunction "NC_1") (pintype "passive+no_connect"))
    )
    (net (code "128") (name "unconnected-(U4-NC-Pad8)") (class "Default")
      (node (ref "U4") (pin "8") (pinfunction "NC_8") (pintype "passive+no_connect"))
    )
    (net (code "129") (name "unconnected-(U5-NC-Pad1)") (class "Default")
      (node (ref "U5") (pin "1") (pinfunction "NC_1") (pintype "passive+no_connect"))
    )
    (net (code "130") (name "unconnected-(U5-NC-Pad4)") (class "Default")
      (node (ref "U5") (pin "4") (pinfunction "NC_4") (pintype "passive+no_connect"))
    )
    (net (code "131") (name "unconnected-(U5-NC-Pad15)") (class "Default")
      (node (ref "U5") (pin "15") (pinfunction "NC_15") (pintype "passive+no_connect"))
    )
    (net (code "132") (name "unconnected-(U6-NC-Pad1)") (class "Default")
      (node (ref "U6") (pin "1") (pinfunction "NC_1") (pintype "passive+no_connect"))
    )
    (net (code "133") (name "unconnected-(U6-NC-Pad4)") (class "Default")
      (node (ref "U6") (pin "4") (pinfunction "NC_4") (pintype "passive+no_connect"))
    )
    (net (code "134") (name "unconnected-(U6-NC-Pad15)") (class "Default")
      (node (ref "U6") (pin "15") (pinfunction "NC_15") (pintype "passive+no_connect"))
    )
    (net (code "135") (name "unconnected-(U7-NC-Pad1)") (class "Default")
      (node (ref "U7") (pin "1") (pinfunction "NC_1") (pintype "passive+no_connect"))
    )
    (net (code "136") (name "unconnected-(U7-NC-Pad8)") (class "Default")
      (node (ref "U7") (pin "8") (pinfunction "NC_8") (pintype "passive+no_connect"))
    )
    (net (code "137") (name "unconnected-(U8-NC-Pad1)") (class "Default")
      (node (ref "U8") (pin "1") (pinfunction "NC_1") (pintype "passive+no_connect"))
    )
    (net (code "138") (name "unconnected-(U8-NC-Pad8)") (class "Default")
      (node (ref "U8") (pin "8") (pinfunction "NC_8") (pintype "passive+no_connect"))
    )
    (net (code "139") (name "unconnected-(U9-ENA-Pad5)") (class "Default")
      (node (ref "U9") (pin "5") (pinfunction "ENA_5") (pintype "passive"))
    )
    (net (code "140") (name "unconnected-(U9-NC-Pad2)") (class "Default")
      (node (ref "U9") (pin "2") (pinfunction "NC_2") (pintype "passive"))
    )
    (net (code "141") (name "unconnected-(U9-NC-Pad3)") (class "Default")
      (node (ref "U9") (pin "3") (pinfunction "NC_3") (pintype "passive"))
    )
    (net (code "142") (name "unconnected-(U11-VREF-Pad5)") (class "Default")
      (node (ref "U11") (pin "5") (pinfunction "VREF_5") (pintype "passive"))
    )
  )
)
